# Transmitter.net
KiCad netlist of a schematic drawn in Altium Designer
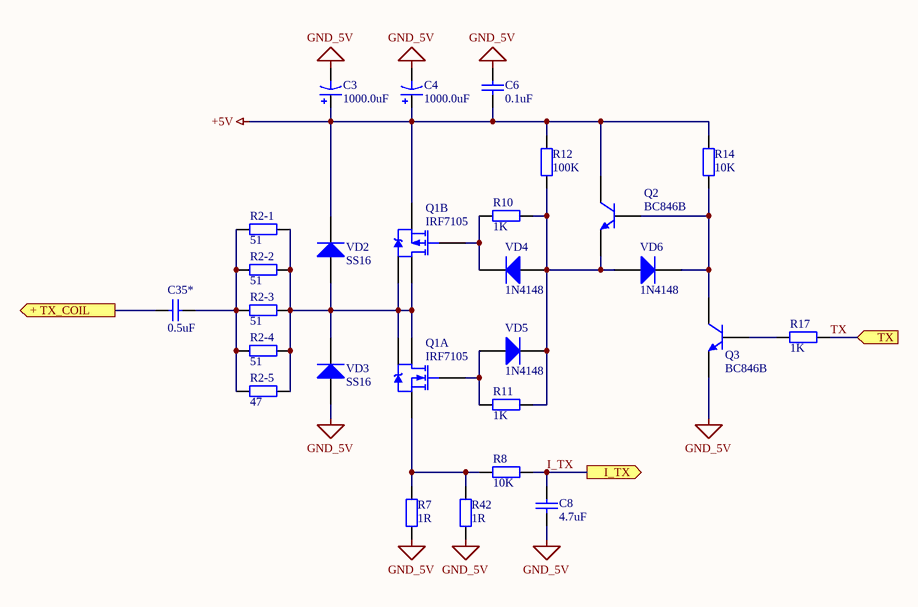
[diagram p0: Transmitter.SchDoc]

(export (version "E")
  (design (tool "Eeschema 10.0.6"))
  (components
    (comp (ref "C3")
      (value "1000.0uF")
      (footprint "Capacitor-10X20-LYINGR")
      (description "Polarized Capacitor (Radial)")
      (fields (field (name "PUBLISHER") "Altium Limited"))
      (libsource (lib "Quasar ARM") (part "Cap Pol1"))
    )
    (comp (ref "C4")
      (value "1000.0uF")
      (footprint "Capacitor-10X20-LYINGR")
      (description "Polarized Capacitor (Radial)")
      (fields (field (name "PUBLISHER") "Altium Limited"))
      (libsource (lib "Quasar ARM") (part "Cap Pol1"))
    )
    (comp (ref "C6")
      (value "0.1uF")
      (footprint "1206_SMD_Capacitor")
      (description "Capacitor")
      (fields (field (name "PUBLISHER") "Altium Limited"))
      (libsource (lib "Quasar ARM") (part "Capacitor SMD"))
    )
    (comp (ref "C8")
      (value "4.7uF")
      (footprint "1206_SMD_Capacitor")
      (description "Capacitor")
      (fields (field (name "PUBLISHER") "Altium Limited"))
      (libsource (lib "Quasar ARM") (part "Capacitor SMD"))
    )
    (comp (ref "C35*")
      (value "0.5uF")
      (footprint "K71-7-LYING")
      (description "Capacitor")
      (fields (field (name "PUBLISHER") "Altium Limited"))
      (libsource (lib "Quasar ARM") (part "Capacitor K71-7"))
    )
    (comp (ref "Q1") (value "IRF7105") (footprint "SO-2") (libsource (lib "Quasar ARM") (part "IRF7105")))
    (comp (ref "Q2")
      (value "BC846B")
      (footprint "SOT23_N")
      (description "NPN General-purpose Transistor")
      (fields (field (name "PUBLISHER") "Altium Limited"))
      (libsource (lib "Quasar ARM") (part "BC846B"))
    )
    (comp (ref "Q3")
      (value "BC846B")
      (footprint "SOT23_N")
      (description "NPN General-purpose Transistor")
      (fields (field (name "PUBLISHER") "Altium Limited"))
      (libsource (lib "Quasar ARM") (part "BC846B"))
    )
    (comp (ref "R2-1")
      (value "51")
      (footprint "1206_SMD_Resistor")
      (description "Resistor")
      (fields (field (name "PUBLISHER") "Altium Limited"))
      (libsource (lib "Quasar ARM") (part "Resistor"))
    )
    (comp (ref "R2-2")
      (value "51")
      (footprint "1206_SMD_Resistor")
      (description "Resistor")
      (fields (field (name "PUBLISHER") "Altium Limited"))
      (libsource (lib "Quasar ARM") (part "Resistor"))
    )
    (comp (ref "R2-3")
      (value "51")
      (footprint "1206_SMD_Resistor")
      (description "Resistor")
      (fields (field (name "PUBLISHER") "Altium Limited"))
      (libsource (lib "Quasar ARM") (part "Resistor"))
    )
    (comp (ref "R2-4")
      (value "51")
      (footprint "1206_SMD_Resistor")
      (description "Resistor")
      (fields (field (name "PUBLISHER") "Altium Limited"))
      (libsource (lib "Quasar ARM") (part "Resistor"))
    )
    (comp (ref "R2-5")
      (value "47")
      (footprint "1206_SMD_Resistor")
      (description "Resistor")
      (fields (field (name "PUBLISHER") "Altium Limited"))
      (libsource (lib "Quasar ARM") (part "Resistor"))
    )
    (comp (ref "R7")
      (value "1R")
      (footprint "1206_SMD_Resistor")
      (description "Resistor")
      (fields (field (name "PUBLISHER") "Altium Limited"))
      (libsource (lib "") (part "Resistor_1"))
    )
    (comp (ref "R8")
      (value "10K")
      (footprint "1206_SMD_Resistor")
      (description "Resistor")
      (fields (field (name "PUBLISHER") "Altium Limited"))
      (libsource (lib "") (part "Resistor_2"))
    )
    (comp (ref "R10")
      (value "1K")
      (footprint "1206_SMD_Resistor")
      (description "Resistor")
      (fields (field (name "PUBLISHER") "Altium Limited"))
      (libsource (lib "") (part "Resistor_2"))
    )
    (comp (ref "R11")
      (value "1K")
      (footprint "1206_SMD_Resistor")
      (description "Resistor")
      (fields (field (name "PUBLISHER") "Altium Limited"))
      (libsource (lib "") (part "Resistor_2"))
    )
    (comp (ref "R12")
      (value "100K")
      (footprint "1206_SMD_Resistor")
      (description "Resistor")
      (fields (field (name "PUBLISHER") "Altium Limited"))
      (libsource (lib "") (part "Resistor_3"))
    )
    (comp (ref "R14")
      (value "10K")
      (footprint "1206_SMD_Resistor")
      (description "Resistor")
      (fields (field (name "PUBLISHER") "Altium Limited"))
      (libsource (lib "") (part "Resistor_3"))
    )
    (comp (ref "R17")
      (value "1K")
      (footprint "1206_SMD_Resistor")
      (description "Resistor")
      (fields (field (name "PUBLISHER") "Altium Limited"))
      (libsource (lib "Quasar ARM") (part "Resistor"))
    )
    (comp (ref "R42")
      (value "1R")
      (footprint "1206_SMD_Resistor")
      (description "Resistor")
      (fields (field (name "PUBLISHER") "Altium Limited"))
      (libsource (lib "") (part "Resistor_1"))
    )
    (comp (ref "VD2")
      (value "SS16")
      (footprint "SMA")
      (description "Default Diode")
      (fields (field (name "PUBLISHER") "Altium Limited"))
      (libsource (lib "Quasar ARM") (part "Diode"))
    )
    (comp (ref "VD3")
      (value "SS16")
      (footprint "SMA")
      (description "Default Diode")
      (fields (field (name "PUBLISHER") "Altium Limited"))
      (libsource (lib "Quasar ARM") (part "Diode"))
    )
    (comp (ref "VD4")
      (value "1N4148")
      (footprint "SOD-323")
      (description "High Conductance Fast Diode")
      (fields (field (name "PUBLISHER") "Altium Limited"))
      (libsource (lib "Quasar ARM") (part "1N4148"))
    )
    (comp (ref "VD5")
      (value "1N4148")
      (footprint "SOD-323")
      (description "High Conductance Fast Diode")
      (fields (field (name "PUBLISHER") "Altium Limited"))
      (libsource (lib "Quasar ARM") (part "1N4148"))
    )
    (comp (ref "VD6")
      (value "1N4148")
      (footprint "SOD-323")
      (description "High Conductance Fast Diode")
      (fields (field (name "PUBLISHER") "Altium Limited"))
      (libsource (lib "Quasar ARM") (part "1N4148"))
    )
  )
  (nets
    (net (code "1") (name "+5V") (class "Default")
      (node (ref "C3") (pin "1") (pinfunction "1_1") (pintype "passive"))
      (node (ref "C4") (pin "1") (pinfunction "1_1") (pintype "passive"))
      (node (ref "C6") (pin "1") (pinfunction "1_1") (pintype "passive"))
      (node (ref "Q1") (pin "3") (pinfunction "S_3") (pintype "passive"))
      (node (ref "Q2") (pin "3") (pinfunction "C_3") (pintype "passive"))
      (node (ref "R12") (pin "2") (pinfunction "2_2") (pintype "passive"))
      (node (ref "R14") (pin "2") (pinfunction "2_2") (pintype "passive"))
      (node (ref "VD2") (pin "2") (pinfunction "K_2") (pintype "passive"))
    )
    (net (code "2") (name "/+ TX_COIL") (class "Default")
      (node (ref "C35*") (pin "1") (pinfunction "1_1") (pintype "passive"))
    )
    (net (code "3") (name "/I_TX") (class "Default")
      (node (ref "C8") (pin "2") (pinfunction "2_2") (pintype "passive"))
      (node (ref "R8") (pin "1") (pinfunction "1_1") (pintype "passive"))
    )
    (net (code "4") (name "/TX") (class "Default")
      (node (ref "R17") (pin "2") (pinfunction "2_2") (pintype "passive"))
    )
    (net (code "5") (name "GND_5V") (class "Default")
      (node (ref "C3") (pin "2") (pinfunction "2_2") (pintype "passive"))
      (node (ref "C4") (pin "2") (pinfunction "2_2") (pintype "passive"))
      (node (ref "C6") (pin "2") (pinfunction "2_2") (pintype "passive"))
      (node (ref "C8") (pin "1") (pinfunction "1_1") (pintype "passive"))
      (node (ref "Q3") (pin "2") (pinfunction "E_2") (pintype "passive"))
      (node (ref "R42") (pin "2") (pinfunction "2_2") (pintype "passive"))
      (node (ref "R7") (pin "2") (pinfunction "2_2") (pintype "passive"))
      (node (ref "VD3") (pin "1") (pinfunction "A_1") (pintype "passive"))
    )
    (net (code "6") (name "Net-(C35*-Pad2)") (class "Default")
      (node (ref "C35*") (pin "2") (pinfunction "2_2") (pintype "passive"))
      (node (ref "R2-1") (pin "1") (pinfunction "1_1") (pintype "passive"))
      (node (ref "R2-2") (pin "1") (pinfunction "1_1") (pintype "passive"))
      (node (ref "R2-3") (pin "1") (pinfunction "1_1") (pintype "passive"))
      (node (ref "R2-4") (pin "1") (pinfunction "1_1") (pintype "passive"))
      (node (ref "R2-5") (pin "1") (pinfunction "1_1") (pintype "passive"))
    )
    (net (code "7") (name "Net-(Q1A-D)") (class "Default")
      (node (ref "Q1") (pin "5") (pinfunction "D_5") (pintype "passive"))
      (node (ref "Q1") (pin "6") (pinfunction "6_6") (pintype "passive"))
      (node (ref "Q1") (pin "7") (pinfunction "D_7") (pintype "passive"))
      (node (ref "Q1") (pin "8") (pinfunction "8_8") (pintype "passive"))
      (node (ref "R2-1") (pin "2") (pinfunction "2_2") (pintype "passive"))
      (node (ref "R2-2") (pin "2") (pinfunction "2_2") (pintype "passive"))
      (node (ref "R2-3") (pin "2") (pinfunction "2_2") (pintype "passive"))
      (node (ref "R2-4") (pin "2") (pinfunction "2_2") (pintype "passive"))
      (node (ref "R2-5") (pin "2") (pinfunction "2_2") (pintype "passive"))
      (node (ref "VD2") (pin "1") (pinfunction "A_1") (pintype "passive"))
      (node (ref "VD3") (pin "2") (pinfunction "K_2") (pintype "passive"))
    )
    (net (code "8") (name "Net-(Q1A-G)") (class "Default")
      (node (ref "Q1") (pin "2") (pinfunction "G_2") (pintype "passive"))
      (node (ref "R11") (pin "2") (pinfunction "2_2") (pintype "passive"))
      (node (ref "VD5") (pin "1") (pinfunction "A_1") (pintype "passive"))
    )
    (net (code "9") (name "Net-(Q1A-S)") (class "Default")
      (node (ref "Q1") (pin "1") (pinfunction "S_1") (pintype "passive"))
      (node (ref "R42") (pin "1") (pinfunction "1_1") (pintype "passive"))
      (node (ref "R7") (pin "1") (pinfunction "1_1") (pintype "passive"))
      (node (ref "R8") (pin "2") (pinfunction "2_2") (pintype "passive"))
    )
    (net (code "10") (name "Net-(Q1B-G)") (class "Default")
      (node (ref "Q1") (pin "4") (pinfunction "G_4") (pintype "passive"))
      (node (ref "R10") (pin "2") (pinfunction "2_2") (pintype "passive"))
      (node (ref "VD4") (pin "2") (pinfunction "K_2") (pintype "passive"))
    )
    (net (code "11") (name "Net-(Q2-B)") (class "Default")
      (node (ref "Q2") (pin "1") (pinfunction "B_1") (pintype "passive"))
      (node (ref "Q3") (pin "3") (pinfunction "C_3") (pintype "passive"))
      (node (ref "R14") (pin "1") (pinfunction "1_1") (pintype "passive"))
      (node (ref "VD6") (pin "2") (pinfunction "K_2") (pintype "passive"))
    )
    (net (code "12") (name "Net-(Q2-E)") (class "Default")
      (node (ref "Q2") (pin "2") (pinfunction "E_2") (pintype "passive"))
      (node (ref "R10") (pin "1") (pinfunction "1_1") (pintype "passive"))
      (node (ref "R11") (pin "1") (pinfunction "1_1") (pintype "passive"))
      (node (ref "R12") (pin "1") (pinfunction "1_1") (pintype "passive"))
      (node (ref "VD4") (pin "1") (pinfunction "A_1") (pintype "passive"))
      (node (ref "VD5") (pin "2") (pinfunction "K_2") (pintype "passive"))
      (node (ref "VD6") (pin "1") (pinfunction "A_1") (pintype "passive"))
    )
    (net (code "13") (name "Net-(Q3-B)") (class "Default")
      (node (ref "Q3") (pin "1") (pinfunction "B_1") (pintype "passive"))
      (node (ref "R17") (pin "1") (pinfunction "1_1") (pintype "passive"))
    )
  )
)
